# DoorALIM.net
KiCad netlist of a schematic drawn in EAGLE
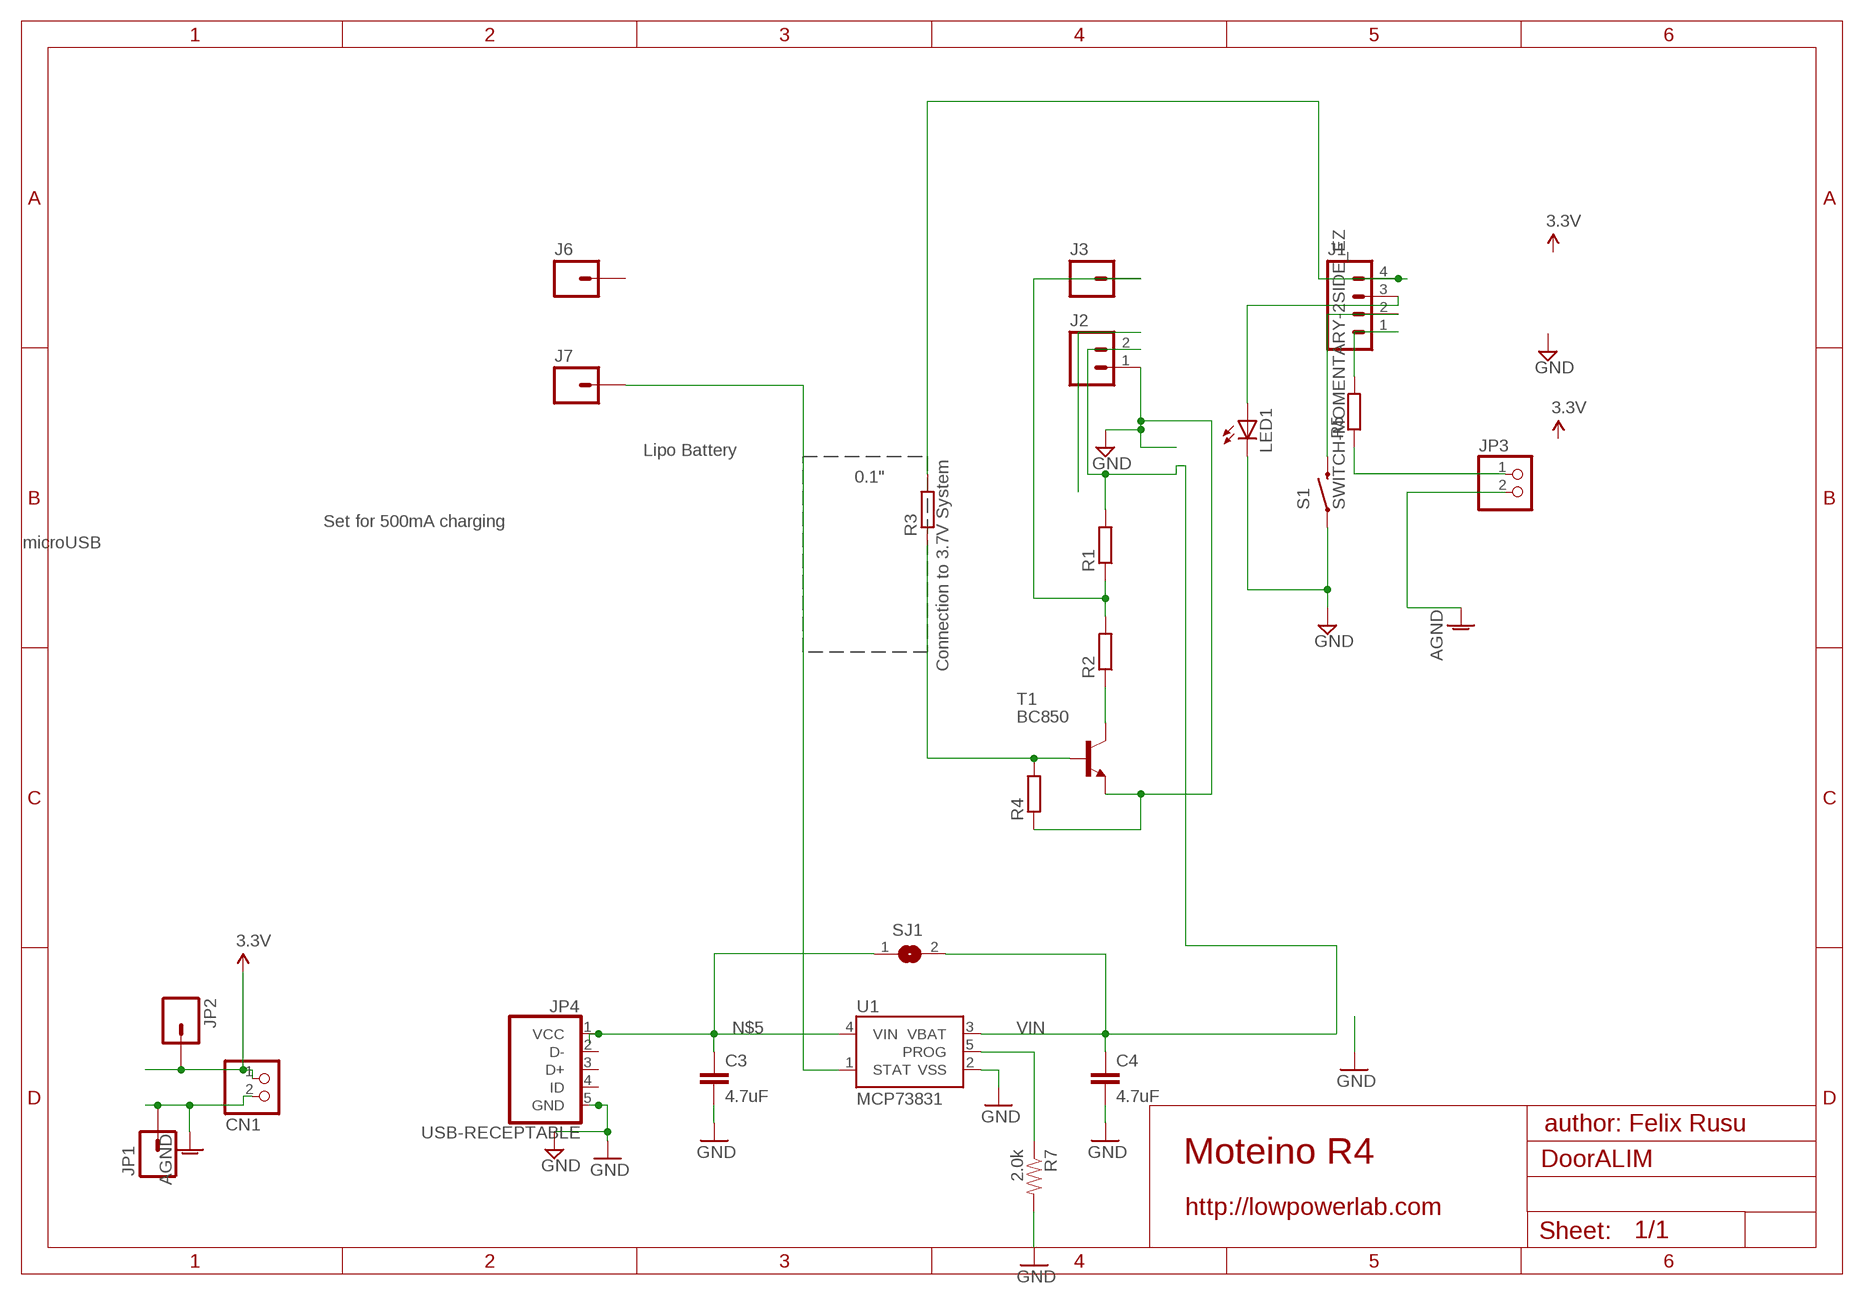
[diagram p0: schematic, sheet 1]

(export (version "E")
  (design (tool "Eeschema 10.0.6"))
  (components
    (comp (ref "C3")
      (value "4.7uF")
      (footprint "eagle-import:0603-CAP")
      (libsource (lib "eagle-import") (part "4.7UF-6.3V-10%(0603)0603"))
    )
    (comp (ref "C4")
      (value "4.7uF")
      (footprint "eagle-import:0603-CAP")
      (libsource (lib "eagle-import") (part "4.7UF-6.3V-10%(0603)0603"))
    )
    (comp (ref "CN1")
      (value "JST_2PIN-SMT")
      (footprint "eagle-import:JST-PH-2-SMT")
      (libsource (lib "eagle-import") (part "JST_2PIN-SMT"))
    )
    (comp (ref "J1")
      (value "M04PTH")
      (footprint "eagle-import:1X04")
      (libsource (lib "eagle-import") (part "M04PTH"))
    )
    (comp (ref "J2")
      (value "M02PTH")
      (footprint "eagle-import:1X02")
      (libsource (lib "eagle-import") (part "M02PTH"))
    )
    (comp (ref "J3")
      (value "M01PTH")
      (footprint "eagle-import:1X01")
      (libsource (lib "eagle-import") (part "M01PTH"))
    )
    (comp (ref "J6")
      (value "M01PTH")
      (footprint "eagle-import:1X01")
      (libsource (lib "eagle-import") (part "M01PTH"))
    )
    (comp (ref "J7")
      (value "M01PTH")
      (footprint "eagle-import:1X01")
      (libsource (lib "eagle-import") (part "M01PTH"))
    )
    (comp (ref "JP1")
      (value "M01PTH")
      (footprint "eagle-import:1X01")
      (libsource (lib "eagle-import") (part "M01PTH"))
    )
    (comp (ref "JP2")
      (value "M01PTH")
      (footprint "eagle-import:1X01")
      (libsource (lib "eagle-import") (part "M01PTH"))
    )
    (comp (ref "JP3")
      (value "PINHD-1X2")
      (footprint "eagle-import:1X02")
      (libsource (lib "eagle-import") (part "PINHD-1X2"))
    )
    (comp (ref "JP4")
      (value "USB-RECEPTABLE")
      (footprint "eagle-import:FCI-10103594-0001LF")
      (libsource (lib "eagle-import") (part "USB-RECEPTABLE"))
    )
    (comp (ref "LED1")
      (value "LED3MM")
      (footprint "eagle-import:LED3MM")
      (libsource (lib "eagle-import") (part "LED3MM"))
    )
    (comp (ref "R1")
      (value "R-EU_0204/7")
      (footprint "eagle-import:0204_7")
      (libsource (lib "eagle-import") (part "R-EU_0204/7"))
    )
    (comp (ref "R2")
      (value "R-EU_0204/7")
      (footprint "eagle-import:0204_7")
      (libsource (lib "eagle-import") (part "R-EU_0204/7"))
    )
    (comp (ref "R3")
      (value "R-EU_M1206")
      (footprint "eagle-import:M1206")
      (libsource (lib "eagle-import") (part "R-EU_M1206"))
    )
    (comp (ref "R4")
      (value "R-EU_M1206")
      (footprint "eagle-import:M1206")
      (libsource (lib "eagle-import") (part "R-EU_M1206"))
    )
    (comp (ref "R5")
      (value "R-EU_0204/7")
      (footprint "eagle-import:0204_7")
      (libsource (lib "eagle-import") (part "R-EU_0204/7"))
    )
    (comp (ref "R7")
      (value "2.0k")
      (footprint "eagle-import:0603-RES")
      (libsource (lib "eagle-import") (part "2.0KOHM1/10W5%(0603)"))
    )
    (comp (ref "S1")
      (value "SWITCH-MOMENTARY-2SIDE_EZ")
      (footprint "eagle-import:TACTILE-PTH-SIDEEZ")
      (libsource (lib "eagle-import") (part "SWITCH-MOMENTARY-2SIDE_EZ"))
    )
    (comp (ref "SJ1") (value "SJ") (footprint "eagle-import:SJ") (libsource (lib "eagle-import") (part "SJ")))
    (comp (ref "T1")
      (value "BC850")
      (footprint "eagle-import:SOT23")
      (libsource (lib "eagle-import") (part "BC850"))
    )
    (comp (ref "U1")
      (value "MCP73831")
      (footprint "eagle-import:SOT23-5")
      (libsource (lib "eagle-import") (part "MCP73831"))
    )
  )
  (nets
    (net (code "1") (name "/N$5") (class "Default")
      (node (ref "C3") (pin "1") (pinfunction "1_1") (pintype "passive"))
      (node (ref "JP4") (pin "1") (pinfunction "VCC_1") (pintype "bidirectional"))
      (node (ref "SJ1") (pin "1") (pinfunction "1_1") (pintype "passive"))
      (node (ref "U1") (pin "4") (pinfunction "VIN_4") (pintype "power_in"))
    )
    (net (code "2") (name "/VIN") (class "Default")
      (node (ref "C4") (pin "1") (pinfunction "1_1") (pintype "passive"))
      (node (ref "J2") (pin "2") (pinfunction "2_2") (pintype "passive"))
      (node (ref "R1") (pin "2") (pinfunction "2_2") (pintype "passive"))
      (node (ref "SJ1") (pin "2") (pinfunction "2_2") (pintype "passive"))
      (node (ref "U1") (pin "3") (pinfunction "VBAT_3") (pintype "power_in"))
    )
    (net (code "3") (name "3.3V") (class "Default")
      (node (ref "CN1") (pin "1") (pinfunction "2_1") (pintype "passive"))
      (node (ref "JP2") (pin "1") (pinfunction "1_1") (pintype "passive"))
    )
    (net (code "4") (name "AGND") (class "Default")
      (node (ref "CN1") (pin "2") (pinfunction "1_2") (pintype "passive"))
      (node (ref "JP1") (pin "1") (pinfunction "1_1") (pintype "passive"))
      (node (ref "JP3") (pin "2") (pinfunction "2_2") (pintype "passive"))
    )
    (net (code "5") (name "GND") (class "Default")
      (node (ref "C3") (pin "2") (pinfunction "2_2") (pintype "passive"))
      (node (ref "C4") (pin "2") (pinfunction "2_2") (pintype "passive"))
      (node (ref "J2") (pin "1") (pinfunction "1_1") (pintype "passive"))
      (node (ref "JP4") (pin "5") (pinfunction "GND_5") (pintype "bidirectional"))
      (node (ref "LED1") (pin "K") (pinfunction "C_K") (pintype "passive"))
      (node (ref "R4") (pin "1") (pinfunction "1_1") (pintype "passive"))
      (node (ref "R7") (pin "2") (pinfunction "2_2") (pintype "passive"))
      (node (ref "S1") (pin "1") (pinfunction "1_1") (pintype "passive"))
      (node (ref "T1") (pin "2") (pinfunction "E_2") (pintype "passive"))
      (node (ref "U1") (pin "2") (pinfunction "VSS_2") (pintype "power_in"))
    )
    (net (code "6") (name "Net-(J1-Pad1)") (class "Default")
      (node (ref "J1") (pin "1") (pinfunction "1_1") (pintype "passive"))
      (node (ref "R5") (pin "2") (pinfunction "2_2") (pintype "passive"))
    )
    (net (code "7") (name "Net-(J1-Pad2)") (class "Default")
      (node (ref "J1") (pin "2") (pinfunction "2_2") (pintype "passive"))
      (node (ref "S1") (pin "2") (pinfunction "2_2") (pintype "passive"))
    )
    (net (code "8") (name "Net-(J1-Pad3)") (class "Default")
      (node (ref "J1") (pin "3") (pinfunction "3_3") (pintype "passive"))
      (node (ref "LED1") (pin "A") (pinfunction "A_A") (pintype "passive"))
    )
    (net (code "9") (name "Net-(J1-Pad4)") (class "Default")
      (node (ref "J1") (pin "4") (pinfunction "4_4") (pintype "passive"))
      (node (ref "R3") (pin "2") (pinfunction "2_2") (pintype "passive"))
    )
    (net (code "10") (name "Net-(J3-Pad1)") (class "Default")
      (node (ref "J3") (pin "1") (pinfunction "1_1") (pintype "passive"))
      (node (ref "R1") (pin "1") (pinfunction "1_1") (pintype "passive"))
      (node (ref "R2") (pin "2") (pinfunction "2_2") (pintype "passive"))
    )
    (net (code "11") (name "Net-(JP3-Pad1)") (class "Default")
      (node (ref "JP3") (pin "1") (pinfunction "1_1") (pintype "passive"))
      (node (ref "R5") (pin "1") (pinfunction "1_1") (pintype "passive"))
    )
    (net (code "12") (name "Net-(T1-B)") (class "Default")
      (node (ref "R3") (pin "1") (pinfunction "1_1") (pintype "passive"))
      (node (ref "R4") (pin "2") (pinfunction "2_2") (pintype "passive"))
      (node (ref "T1") (pin "1") (pinfunction "B_1") (pintype "passive"))
    )
    (net (code "13") (name "Net-(T1-C)") (class "Default")
      (node (ref "R2") (pin "1") (pinfunction "1_1") (pintype "passive"))
      (node (ref "T1") (pin "3") (pinfunction "C_3") (pintype "passive"))
    )
    (net (code "14") (name "Net-(U1-PROG)") (class "Default")
      (node (ref "R7") (pin "1") (pinfunction "1_1") (pintype "passive"))
      (node (ref "U1") (pin "5") (pinfunction "PROG_5") (pintype "input"))
    )
    (net (code "15") (name "Net-(U1-STAT)") (class "Default")
      (node (ref "J7") (pin "1") (pinfunction "1_1") (pintype "passive"))
      (node (ref "U1") (pin "1") (pinfunction "STAT_1") (pintype "output"))
    )
    (net (code "16") (name "unconnected-(J6-Pad1)") (class "Default")
      (node (ref "J6") (pin "1") (pinfunction "1_1") (pintype "passive"))
    )
    (net (code "17") (name "unconnected-(JP4-D+-Pad3)") (class "Default")
      (node (ref "JP4") (pin "3") (pinfunction "D+_3") (pintype "bidirectional"))
    )
    (net (code "18") (name "unconnected-(JP4-D--Pad2)") (class "Default")
      (node (ref "JP4") (pin "2") (pinfunction "D-_2") (pintype "bidirectional"))
    )
    (net (code "19") (name "unconnected-(JP4-ID-Pad4)") (class "Default")
      (node (ref "JP4") (pin "4") (pinfunction "ID_4") (pintype "bidirectional"))
    )
  )
)
